# ESP8266_MySensorsGateway_v1_3_2.net
KiCad netlist of a schematic drawn in EAGLE
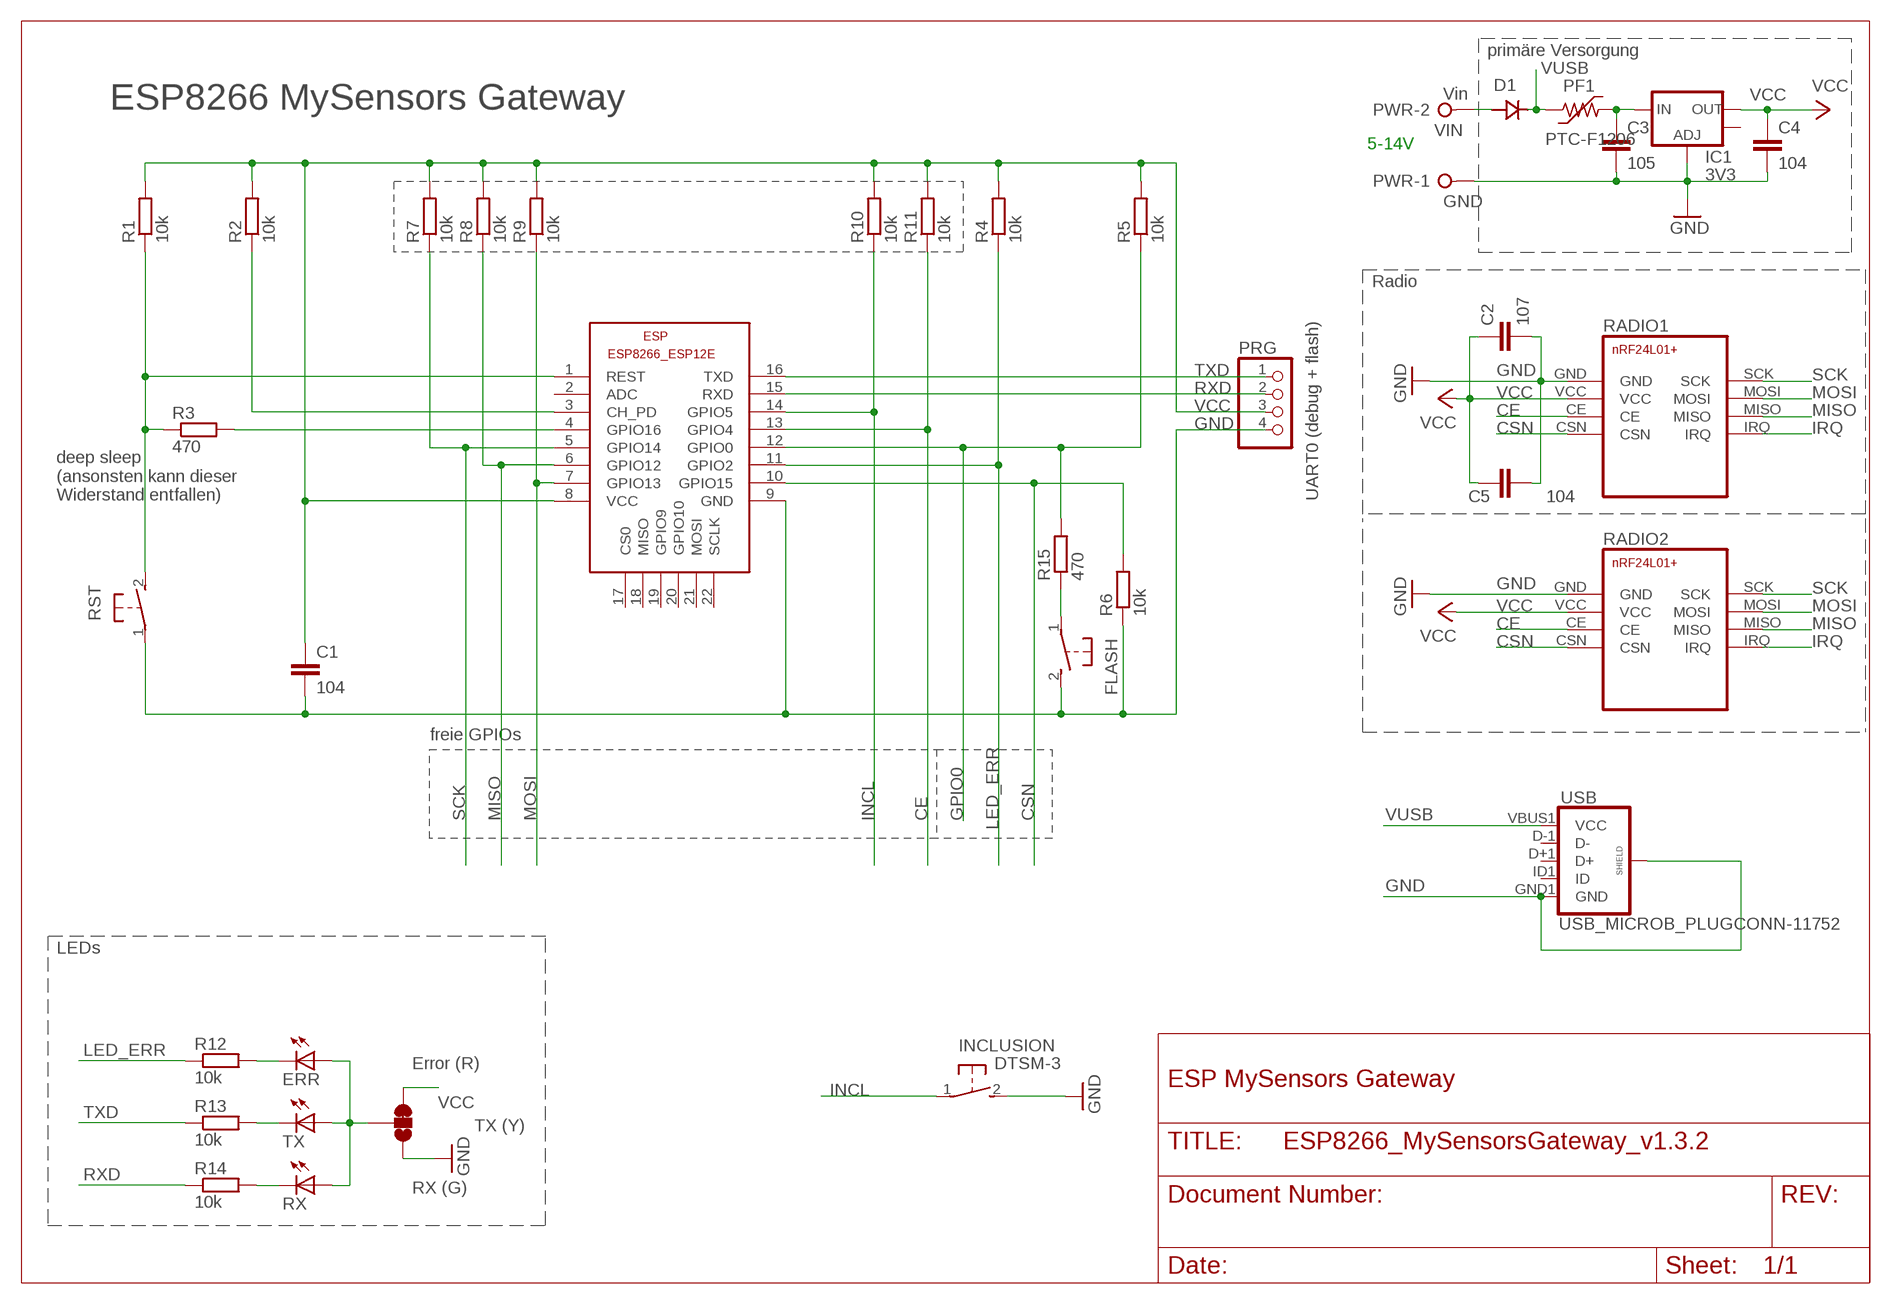
[diagram p0: schematic, sheet 1]

(export (version "E")
  (design (tool "Eeschema 10.0.6"))
  (components
    (comp (ref "C1")
      (value "104")
      (footprint "eagle-import:C0805")
      (libsource (lib "eagle-import") (part "C-EUC0805"))
    )
    (comp (ref "C2")
      (value "107")
      (footprint "eagle-import:MY1210")
      (libsource (lib "eagle-import") (part "C"))
    )
    (comp (ref "C3")
      (value "105")
      (footprint "eagle-import:C0805")
      (libsource (lib "eagle-import") (part "C-EUC0805"))
    )
    (comp (ref "C4")
      (value "104")
      (footprint "eagle-import:C0805")
      (libsource (lib "eagle-import") (part "C-EUC0805"))
    )
    (comp (ref "C5")
      (value "104")
      (footprint "eagle-import:C0805")
      (libsource (lib "eagle-import") (part "C-EUC0805"))
    )
    (comp (ref "D1")
      (value "SS14")
      (footprint "eagle-import:DO214")
      (libsource (lib "eagle-import") (part "SS14"))
    )
    (comp (ref "ERR")
      (value "R")
      (footprint "eagle-import:CHIPLED_1206")
      (libsource (lib "eagle-import") (part "LEDCHIPLED_1206"))
    )
    (comp (ref "ESP")
      (value "µC")
      (footprint "eagle-import:ESP8266-ESP12E")
      (libsource (lib "eagle-import") (part "ESP8266-12EESP8266-ESP12E"))
    )
    (comp (ref "FLASH")
      (value "DTSM-3")
      (footprint "eagle-import:DTSM-3")
      (libsource (lib "eagle-import") (part "DTSM-3"))
    )
    (comp (ref "IC1")
      (value "3V3")
      (footprint "eagle-import:SOT223")
      (libsource (lib "eagle-import") (part "V_REG_LM1117SOT223"))
    )
    (comp (ref "INCLUSION")
      (value "DTSM-3")
      (footprint "eagle-import:DTSM-3")
      (libsource (lib "eagle-import") (part "DTSM-3"))
    )
    (comp (ref "PF1")
      (value "PTC-F1206")
      (footprint "eagle-import:F1206")
      (libsource (lib "eagle-import") (part "PTC-F1206"))
    )
    (comp (ref "PRG")
      (value "PINHD-1X4_S")
      (footprint "eagle-import:1X04")
      (libsource (lib "eagle-import") (part "PINHD-1X4_S"))
    )
    (comp (ref "PWR")
      (value "Vin")
      (footprint "eagle-import:W237-132")
      (libsource (lib "eagle-import") (part "W237-02P"))
    )
    (comp (ref "R1")
      (value "10k")
      (footprint "eagle-import:R0805")
      (libsource (lib "eagle-import") (part "resistor_R-EU_R0805"))
    )
    (comp (ref "R2")
      (value "10k")
      (footprint "eagle-import:R0805")
      (libsource (lib "eagle-import") (part "resistor_R-EU_R0805"))
    )
    (comp (ref "R3")
      (value "470")
      (footprint "eagle-import:R0805")
      (libsource (lib "eagle-import") (part "resistor_R-EU_R0805"))
    )
    (comp (ref "R4")
      (value "10k")
      (footprint "eagle-import:R0805")
      (libsource (lib "eagle-import") (part "resistor_R-EU_R0805"))
    )
    (comp (ref "R5")
      (value "10k")
      (footprint "eagle-import:R0805")
      (libsource (lib "eagle-import") (part "resistor_R-EU_R0805"))
    )
    (comp (ref "R6")
      (value "10k")
      (footprint "eagle-import:R0805")
      (libsource (lib "eagle-import") (part "resistor_R-EU_R0805"))
    )
    (comp (ref "R7")
      (value "10k")
      (footprint "eagle-import:R0805")
      (libsource (lib "eagle-import") (part "resistor_R-EU_R0805"))
    )
    (comp (ref "R8")
      (value "10k")
      (footprint "eagle-import:R0805")
      (libsource (lib "eagle-import") (part "resistor_R-EU_R0805"))
    )
    (comp (ref "R9")
      (value "10k")
      (footprint "eagle-import:R0805")
      (libsource (lib "eagle-import") (part "resistor_R-EU_R0805"))
    )
    (comp (ref "R10")
      (value "10k")
      (footprint "eagle-import:R0805")
      (libsource (lib "eagle-import") (part "resistor_R-EU_R0805"))
    )
    (comp (ref "R11")
      (value "10k")
      (footprint "eagle-import:R0805")
      (libsource (lib "eagle-import") (part "resistor_R-EU_R0805"))
    )
    (comp (ref "R12")
      (value "10k")
      (footprint "eagle-import:R0805")
      (libsource (lib "eagle-import") (part "R-EU_R0805"))
    )
    (comp (ref "R13")
      (value "10k")
      (footprint "eagle-import:R0805")
      (libsource (lib "eagle-import") (part "R-EU_R0805"))
    )
    (comp (ref "R14")
      (value "10k")
      (footprint "eagle-import:R0805")
      (libsource (lib "eagle-import") (part "R-EU_R0805"))
    )
    (comp (ref "R15")
      (value "470")
      (footprint "eagle-import:R0805")
      (libsource (lib "eagle-import") (part "resistor_R-EU_R0805"))
    )
    (comp (ref "RADIO1")
      (value "NRF24L01+")
      (footprint "eagle-import:NRF24L01+")
      (libsource (lib "eagle-import") (part "NRF24L01+"))
    )
    (comp (ref "RADIO2")
      (value "NRF24L01+NRF24L01+MINI")
      (footprint "eagle-import:NRF24L01+MINI")
      (libsource (lib "eagle-import") (part "NRF24L01+NRF24L01+MINI"))
    )
    (comp (ref "RST")
      (value "DTSM-3")
      (footprint "eagle-import:DTSM-3")
      (libsource (lib "eagle-import") (part "DTSM-3"))
    )
    (comp (ref "RX")
      (value "G")
      (footprint "eagle-import:CHIPLED_1206")
      (libsource (lib "eagle-import") (part "LEDCHIPLED_1206"))
    )
    (comp (ref "SJ1")
      (value "JUMPER-PAD-3-2OF3_NC_BY_TRACE_SMALL")
      (footprint "eagle-import:PAD-JUMPER-3-2OF3_NC_BY_TRACE_YES_SILK_FULL_BOX")
      (libsource (lib "eagle-import") (part "JUMPER-PAD-3-2OF3_NC_BY_TRACE_SMALL"))
    )
    (comp (ref "TX")
      (value "Y")
      (footprint "eagle-import:CHIPLED_1206")
      (libsource (lib "eagle-import") (part "LEDCHIPLED_1206"))
    )
    (comp (ref "USB")
      (value "USB_MICROB_PLUGCONN-11752")
      (footprint "eagle-import:USB-B-MICRO-SMD_V03")
      (libsource (lib "eagle-import") (part "USB_MICROB_PLUGCONN-11752"))
    )
  )
  (nets
    (net (code "1") (name "/CE") (class "Default")
      (node (ref "ESP") (pin "13") (pinfunction "GPIO4_13") (pintype "bidirectional"))
      (node (ref "R11") (pin "1") (pinfunction "1_1") (pintype "passive"))
      (node (ref "RADIO1") (pin "CE") (pinfunction "CE_CE") (pintype "bidirectional"))
      (node (ref "RADIO2") (pin "CE") (pinfunction "CE_CE") (pintype "bidirectional"))
    )
    (net (code "2") (name "/CSN") (class "Default")
      (node (ref "ESP") (pin "10") (pinfunction "GPIO15_10") (pintype "bidirectional"))
      (node (ref "R6") (pin "2") (pinfunction "2_2") (pintype "passive"))
      (node (ref "RADIO1") (pin "CSN") (pinfunction "CSN_CSN") (pintype "bidirectional"))
      (node (ref "RADIO2") (pin "CSN") (pinfunction "CSN_CSN") (pintype "bidirectional"))
    )
    (net (code "3") (name "/GPIO0") (class "Default")
      (node (ref "ESP") (pin "12") (pinfunction "GPIO0_12") (pintype "bidirectional"))
      (node (ref "R15") (pin "2") (pinfunction "2_2") (pintype "passive"))
      (node (ref "R5") (pin "1") (pinfunction "1_1") (pintype "passive"))
    )
    (net (code "4") (name "/INCL") (class "Default")
      (node (ref "ESP") (pin "14") (pinfunction "GPIO5_14") (pintype "bidirectional"))
      (node (ref "INCLUSION") (pin "1") (pinfunction "1_1") (pintype "passive"))
      (node (ref "R10") (pin "1") (pinfunction "1_1") (pintype "passive"))
    )
    (net (code "5") (name "/IRQ") (class "Default")
      (node (ref "RADIO1") (pin "IRQ") (pinfunction "IRQ_IRQ") (pintype "bidirectional"))
      (node (ref "RADIO2") (pin "IRQ") (pinfunction "IRQ_IRQ") (pintype "bidirectional"))
    )
    (net (code "6") (name "/LED_ERR") (class "Default")
      (node (ref "ESP") (pin "11") (pinfunction "GPIO2_11") (pintype "bidirectional"))
      (node (ref "R12") (pin "1") (pinfunction "1_1") (pintype "passive"))
      (node (ref "R4") (pin "1") (pinfunction "1_1") (pintype "passive"))
    )
    (net (code "7") (name "/MISO") (class "Default")
      (node (ref "ESP") (pin "6") (pinfunction "GPIO12_6") (pintype "bidirectional"))
      (node (ref "R8") (pin "1") (pinfunction "1_1") (pintype "passive"))
      (node (ref "RADIO1") (pin "MISO") (pinfunction "MISO_MISO") (pintype "bidirectional"))
      (node (ref "RADIO2") (pin "MISO") (pinfunction "MISO_MISO") (pintype "bidirectional"))
    )
    (net (code "8") (name "/MOSI") (class "Default")
      (node (ref "ESP") (pin "7") (pinfunction "GPIO13_7") (pintype "bidirectional"))
      (node (ref "R9") (pin "1") (pinfunction "1_1") (pintype "passive"))
      (node (ref "RADIO1") (pin "MOSI") (pinfunction "MOSI_MOSI") (pintype "bidirectional"))
      (node (ref "RADIO2") (pin "MOSI") (pinfunction "MOSI_MOSI") (pintype "bidirectional"))
    )
    (net (code "9") (name "/RXD") (class "Default")
      (node (ref "ESP") (pin "15") (pinfunction "RXD_15") (pintype "bidirectional"))
      (node (ref "PRG") (pin "2") (pinfunction "2_2") (pintype "passive"))
      (node (ref "R14") (pin "1") (pinfunction "1_1") (pintype "passive"))
    )
    (net (code "10") (name "/SCK") (class "Default")
      (node (ref "ESP") (pin "5") (pinfunction "GPIO14_5") (pintype "bidirectional"))
      (node (ref "R7") (pin "1") (pinfunction "1_1") (pintype "passive"))
      (node (ref "RADIO1") (pin "SCK") (pinfunction "SCK_SCK") (pintype "bidirectional"))
      (node (ref "RADIO2") (pin "SCK") (pinfunction "SCK_SCK") (pintype "bidirectional"))
    )
    (net (code "11") (name "/TXD") (class "Default")
      (node (ref "ESP") (pin "16") (pinfunction "TXD_16") (pintype "bidirectional"))
      (node (ref "PRG") (pin "1") (pinfunction "1_1") (pintype "passive"))
      (node (ref "R13") (pin "1") (pinfunction "1_1") (pintype "passive"))
    )
    (net (code "12") (name "/VIN") (class "Default")
      (node (ref "D1") (pin "ANODE") (pinfunction "ANODE_ANODE") (pintype "bidirectional"))
      (node (ref "PWR") (pin "2") (pinfunction "KL_2") (pintype "passive"))
    )
    (net (code "13") (name "/VUSB") (class "Default")
      (node (ref "D1") (pin "CATHODE") (pinfunction "CATHODE_CATHODE") (pintype "bidirectional"))
      (node (ref "PF1") (pin "1") (pinfunction "1_1") (pintype "passive"))
      (node (ref "USB") (pin "VBUS1") (pinfunction "VCC_VBUS1") (pintype "bidirectional"))
    )
    (net (code "14") (name "GND") (class "Default")
      (node (ref "C1") (pin "2") (pinfunction "2_2") (pintype "passive"))
      (node (ref "C2") (pin "2") (pinfunction "2_2") (pintype "passive"))
      (node (ref "C3") (pin "2") (pinfunction "2_2") (pintype "passive"))
      (node (ref "C4") (pin "2") (pinfunction "2_2") (pintype "passive"))
      (node (ref "C5") (pin "2") (pinfunction "2_2") (pintype "passive"))
      (node (ref "ESP") (pin "9") (pinfunction "GND_9") (pintype "bidirectional"))
      (node (ref "FLASH") (pin "2") (pinfunction "2_2") (pintype "passive"))
      (node (ref "IC1") (pin "1") (pinfunction "ADJ_1") (pintype "input"))
      (node (ref "INCLUSION") (pin "2") (pinfunction "2_2") (pintype "passive"))
      (node (ref "PRG") (pin "4") (pinfunction "4_4") (pintype "passive"))
      (node (ref "PWR") (pin "1") (pinfunction "KL_1") (pintype "passive"))
      (node (ref "R6") (pin "1") (pinfunction "1_1") (pintype "passive"))
      (node (ref "RADIO1") (pin "GND") (pinfunction "GND_GND") (pintype "power_in"))
      (node (ref "RADIO2") (pin "GND") (pinfunction "GND_GND") (pintype "power_in"))
      (node (ref "RST") (pin "1") (pinfunction "1_1") (pintype "passive"))
      (node (ref "SJ1") (pin "1") (pinfunction "1_1") (pintype "passive"))
      (node (ref "USB") (pin "GND1") (pinfunction "GND_GND1") (pintype "bidirectional"))
      (node (ref "USB") (pin "SHIELD1") (pinfunction "SHIELD_SHIELD1") (pintype "bidirectional"))
      (node (ref "USB") (pin "SHIELD2") (pinfunction "SHIELD_SHIELD2") (pintype "bidirectional"))
      (node (ref "USB") (pin "SHIELD3") (pinfunction "SHIELD_SHIELD3") (pintype "bidirectional"))
    )
    (net (code "15") (name "Net-(ERR-PadA)") (class "Default")
      (node (ref "ERR") (pin "A") (pinfunction "A_A") (pintype "passive"))
      (node (ref "RX") (pin "A") (pinfunction "A_A") (pintype "passive"))
      (node (ref "SJ1") (pin "2") (pinfunction "2_2") (pintype "passive"))
      (node (ref "TX") (pin "A") (pinfunction "A_A") (pintype "passive"))
    )
    (net (code "16") (name "Net-(ERR-PadC)") (class "Default")
      (node (ref "ERR") (pin "C") (pinfunction "C_C") (pintype "passive"))
      (node (ref "R12") (pin "2") (pinfunction "2_2") (pintype "passive"))
    )
    (net (code "17") (name "Net-(ESP-CH_PD)") (class "Default")
      (node (ref "ESP") (pin "3") (pinfunction "CH_PD_3") (pintype "bidirectional"))
      (node (ref "R2") (pin "1") (pinfunction "1_1") (pintype "passive"))
    )
    (net (code "18") (name "Net-(ESP-GPIO16)") (class "Default")
      (node (ref "ESP") (pin "4") (pinfunction "GPIO16_4") (pintype "bidirectional"))
      (node (ref "R3") (pin "2") (pinfunction "2_2") (pintype "passive"))
    )
    (net (code "19") (name "Net-(ESP-REST)") (class "Default")
      (node (ref "ESP") (pin "1") (pinfunction "REST_1") (pintype "bidirectional"))
      (node (ref "R1") (pin "1") (pinfunction "1_1") (pintype "passive"))
      (node (ref "R3") (pin "1") (pinfunction "1_1") (pintype "passive"))
      (node (ref "RST") (pin "2") (pinfunction "2_2") (pintype "passive"))
    )
    (net (code "20") (name "Net-(FLASH-Pad1)") (class "Default")
      (node (ref "FLASH") (pin "1") (pinfunction "1_1") (pintype "passive"))
      (node (ref "R15") (pin "1") (pinfunction "1_1") (pintype "passive"))
    )
    (net (code "21") (name "Net-(IC1-IN)") (class "Default")
      (node (ref "C3") (pin "1") (pinfunction "1_1") (pintype "passive"))
      (node (ref "IC1") (pin "3") (pinfunction "IN_3") (pintype "input"))
      (node (ref "PF1") (pin "2") (pinfunction "2_2") (pintype "passive"))
    )
    (net (code "22") (name "Net-(R13-Pad2)") (class "Default")
      (node (ref "R13") (pin "2") (pinfunction "2_2") (pintype "passive"))
      (node (ref "TX") (pin "C") (pinfunction "C_C") (pintype "passive"))
    )
    (net (code "23") (name "Net-(R14-Pad2)") (class "Default")
      (node (ref "R14") (pin "2") (pinfunction "2_2") (pintype "passive"))
      (node (ref "RX") (pin "C") (pinfunction "C_C") (pintype "passive"))
    )
    (net (code "24") (name "VCC") (class "Default")
      (node (ref "C1") (pin "1") (pinfunction "1_1") (pintype "passive"))
      (node (ref "C2") (pin "1") (pinfunction "1_1") (pintype "passive"))
      (node (ref "C4") (pin "1") (pinfunction "1_1") (pintype "passive"))
      (node (ref "C5") (pin "1") (pinfunction "1_1") (pintype "passive"))
      (node (ref "ESP") (pin "8") (pinfunction "VCC_8") (pintype "bidirectional"))
      (node (ref "IC1") (pin "2") (pinfunction "OUT_2") (pintype "output"))
      (node (ref "PRG") (pin "3") (pinfunction "3_3") (pintype "passive"))
      (node (ref "R1") (pin "2") (pinfunction "2_2") (pintype "passive"))
      (node (ref "R10") (pin "2") (pinfunction "2_2") (pintype "passive"))
      (node (ref "R11") (pin "2") (pinfunction "2_2") (pintype "passive"))
      (node (ref "R2") (pin "2") (pinfunction "2_2") (pintype "passive"))
      (node (ref "R4") (pin "2") (pinfunction "2_2") (pintype "passive"))
      (node (ref "R5") (pin "2") (pinfunction "2_2") (pintype "passive"))
      (node (ref "R7") (pin "2") (pinfunction "2_2") (pintype "passive"))
      (node (ref "R8") (pin "2") (pinfunction "2_2") (pintype "passive"))
      (node (ref "R9") (pin "2") (pinfunction "2_2") (pintype "passive"))
      (node (ref "RADIO1") (pin "VCC") (pinfunction "VCC_VCC") (pintype "power_in"))
      (node (ref "RADIO2") (pin "VCC") (pinfunction "VCC_VCC") (pintype "power_in"))
      (node (ref "SJ1") (pin "3") (pinfunction "3_3") (pintype "passive"))
    )
    (net (code "25") (name "unconnected-(ESP-ADC-Pad2)") (class "Default")
      (node (ref "ESP") (pin "2") (pinfunction "ADC_2") (pintype "bidirectional"))
    )
    (net (code "26") (name "unconnected-(ESP-CS0-Pad17)") (class "Default")
      (node (ref "ESP") (pin "17") (pinfunction "CS0_17") (pintype "bidirectional"))
    )
    (net (code "27") (name "unconnected-(ESP-GPIO9-Pad19)") (class "Default")
      (node (ref "ESP") (pin "19") (pinfunction "GPIO9_19") (pintype "bidirectional"))
    )
    (net (code "28") (name "unconnected-(ESP-GPIO10-Pad20)") (class "Default")
      (node (ref "ESP") (pin "20") (pinfunction "GPIO10_20") (pintype "bidirectional"))
    )
    (net (code "29") (name "unconnected-(ESP-MISO-Pad18)") (class "Default")
      (node (ref "ESP") (pin "18") (pinfunction "MISO_18") (pintype "bidirectional"))
    )
    (net (code "30") (name "unconnected-(ESP-MOSI-Pad21)") (class "Default")
      (node (ref "ESP") (pin "21") (pinfunction "MOSI_21") (pintype "bidirectional"))
    )
    (net (code "31") (name "unconnected-(ESP-SCLK-Pad22)") (class "Default")
      (node (ref "ESP") (pin "22") (pinfunction "SCLK_22") (pintype "bidirectional"))
    )
    (net (code "32") (name "unconnected-(IC1-OUT-Pad4)") (class "Default")
      (node (ref "IC1") (pin "4") (pinfunction "OUT_4") (pintype "output"))
    )
    (net (code "33") (name "unconnected-(USB-D+-PadD+1)") (class "Default")
      (node (ref "USB") (pin "D+1") (pinfunction "D+_D+1") (pintype "bidirectional"))
    )
    (net (code "34") (name "unconnected-(USB-D--PadD-1)") (class "Default")
      (node (ref "USB") (pin "D-1") (pinfunction "D-_D-1") (pintype "bidirectional"))
    )
    (net (code "35") (name "unconnected-(USB-ID-PadID1)") (class "Default")
      (node (ref "USB") (pin "ID1") (pinfunction "ID_ID1") (pintype "bidirectional"))
    )
  )
)
